# pressure.net
KiCad netlist of a schematic drawn in EAGLE
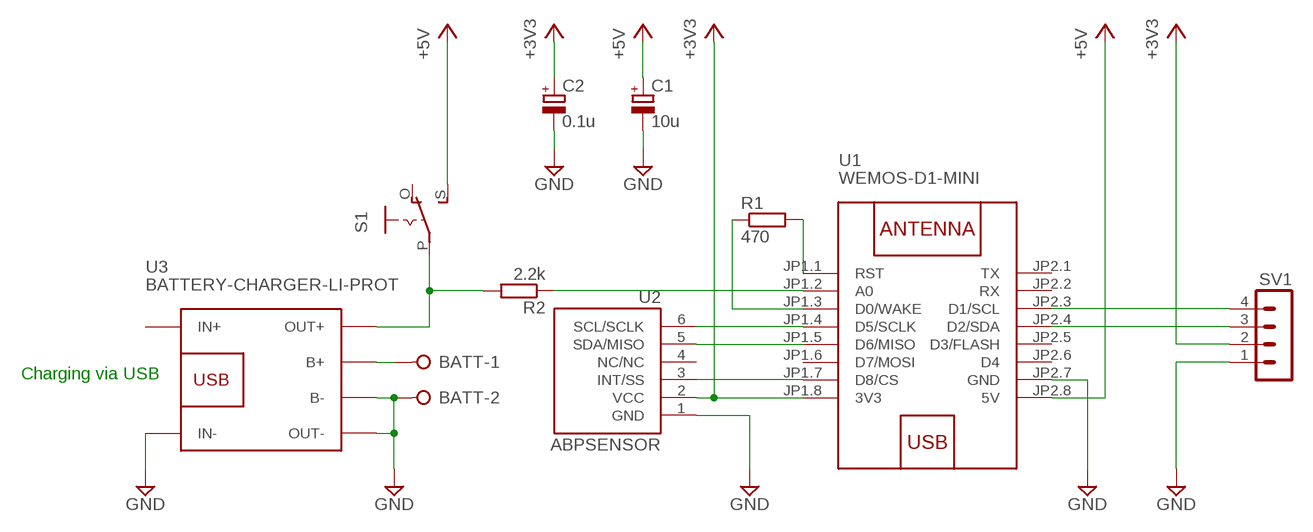
[diagram p0: schematic, sheet 1]

(export (version "E")
  (design (tool "Eeschema 10.0.6"))
  (components
    (comp (ref "BATT")
      (value "W237-02P")
      (footprint "eagle-import:W237-132")
      (libsource (lib "eagle-import") (part "W237-02P"))
    )
    (comp (ref "C1")
      (value "10u")
      (footprint "eagle-import:E2,5-5")
      (libsource (lib "eagle-import") (part "CPOL-EUE2.5-5"))
    )
    (comp (ref "C2")
      (value "0.1u")
      (footprint "eagle-import:E2,5-5")
      (libsource (lib "eagle-import") (part "CPOL-EUE2.5-5"))
    )
    (comp (ref "R1")
      (value "470")
      (footprint "eagle-import:0207_10")
      (libsource (lib "eagle-import") (part "R-EU_0207/10"))
    )
    (comp (ref "R2")
      (value "2.2k")
      (footprint "eagle-import:0207_10")
      (libsource (lib "eagle-import") (part "R-EU_0207/10"))
    )
    (comp (ref "S1")
      (value "EG1218S")
      (footprint "eagle-import:EG1218")
      (libsource (lib "eagle-import") (part "EG1218S"))
    )
    (comp (ref "SV1")
      (value "4-DIGIT-LED")
      (footprint "eagle-import:MA04-1")
      (libsource (lib "eagle-import") (part "MA04-1"))
    )
    (comp (ref "U1")
      (value "WEMOS-D1-MINI")
      (footprint "eagle-import:WEMOS-D1-MINI")
      (libsource (lib "eagle-import") (part "WEMOS-D1-MINI"))
    )
    (comp (ref "U2")
      (value "ABPSENSOR")
      (footprint "eagle-import:ABP-DIP6")
      (libsource (lib "eagle-import") (part "ABPSENSOR"))
    )
    (comp (ref "U3")
      (value "BATTERY-CHARGER-LI-PROT")
      (footprint "eagle-import:BATTERY-CHARGER-LI-PROT")
      (libsource (lib "eagle-import") (part "BATTERY-CHARGER-LI-PROT"))
    )
  )
  (nets
    (net (code "1") (name "+3V3") (class "Default")
      (node (ref "C2") (pin "+") (pinfunction "+_+") (pintype "passive"))
      (node (ref "SV1") (pin "2") (pinfunction "2_2") (pintype "passive"))
      (node (ref "U1") (pin "JP1.8") (pinfunction "3V3_JP1.8") (pintype "power_in"))
      (node (ref "U2") (pin "2") (pinfunction "VCC_2") (pintype "power_in"))
    )
    (net (code "2") (name "+5V") (class "Default")
      (node (ref "C1") (pin "+") (pinfunction "+_+") (pintype "passive"))
      (node (ref "S1") (pin "S") (pinfunction "S_S") (pintype "passive"))
      (node (ref "U1") (pin "JP2.8") (pinfunction "5V_JP2.8") (pintype "power_in"))
    )
    (net (code "3") (name "GND") (class "Default")
      (node (ref "BATT") (pin "2") (pinfunction "KL_2") (pintype "passive"))
      (node (ref "C1") (pin "-") (pinfunction "-_-") (pintype "passive"))
      (node (ref "C2") (pin "-") (pinfunction "-_-") (pintype "passive"))
      (node (ref "SV1") (pin "1") (pinfunction "1_1") (pintype "passive"))
      (node (ref "U1") (pin "JP2.7") (pinfunction "GND_JP2.7") (pintype "power_in"))
      (node (ref "U2") (pin "1") (pinfunction "GND_1") (pintype "power_in"))
      (node (ref "U3") (pin "B-") (pinfunction "B-_B-") (pintype "bidirectional"))
      (node (ref "U3") (pin "IN-") (pinfunction "IN-_IN-") (pintype "bidirectional"))
      (node (ref "U3") (pin "OUT-") (pinfunction "OUT-_OUT-") (pintype "bidirectional"))
    )
    (net (code "4") (name "Net-(BATTA-KL)") (class "Default")
      (node (ref "BATT") (pin "1") (pinfunction "KL_1") (pintype "passive"))
      (node (ref "U3") (pin "B+") (pinfunction "B+_B+") (pintype "bidirectional"))
    )
    (net (code "5") (name "Net-(R2-Pad2)") (class "Default")
      (node (ref "R2") (pin "2") (pinfunction "2_2") (pintype "passive"))
      (node (ref "S1") (pin "P") (pinfunction "P_P") (pintype "passive"))
      (node (ref "U3") (pin "OUT+") (pinfunction "OUT+_OUT+") (pintype "bidirectional"))
    )
    (net (code "6") (name "Net-(U1-A0)") (class "Default")
      (node (ref "R2") (pin "1") (pinfunction "1_1") (pintype "passive"))
      (node (ref "U1") (pin "JP1.2") (pinfunction "A0_JP1.2") (pintype "bidirectional"))
    )
    (net (code "7") (name "Net-(U1-D0{slash}WAKE)") (class "Default")
      (node (ref "R1") (pin "1") (pinfunction "1_1") (pintype "passive"))
      (node (ref "U1") (pin "JP1.3") (pinfunction "D0/WAKE_JP1.3") (pintype "bidirectional"))
    )
    (net (code "8") (name "Net-(U1-D1{slash}SCL)") (class "Default")
      (node (ref "SV1") (pin "4") (pinfunction "4_4") (pintype "passive"))
      (node (ref "U1") (pin "JP2.3") (pinfunction "D1/SCL_JP2.3") (pintype "bidirectional"))
    )
    (net (code "9") (name "Net-(U1-D2{slash}SDA)") (class "Default")
      (node (ref "SV1") (pin "3") (pinfunction "3_3") (pintype "passive"))
      (node (ref "U1") (pin "JP2.4") (pinfunction "D2/SDA_JP2.4") (pintype "bidirectional"))
    )
    (net (code "10") (name "Net-(U1-D5{slash}SCLK)") (class "Default")
      (node (ref "U1") (pin "JP1.4") (pinfunction "D5/SCLK_JP1.4") (pintype "bidirectional"))
      (node (ref "U2") (pin "6") (pinfunction "SCL/SCLK_6") (pintype "bidirectional"))
    )
    (net (code "11") (name "Net-(U1-D6{slash}MISO)") (class "Default")
      (node (ref "U1") (pin "JP1.5") (pinfunction "D6/MISO_JP1.5") (pintype "bidirectional"))
      (node (ref "U2") (pin "5") (pinfunction "SDA/MISO_5") (pintype "bidirectional"))
    )
    (net (code "12") (name "Net-(U1-D8{slash}CS)") (class "Default")
      (node (ref "U1") (pin "JP1.7") (pinfunction "D8/CS_JP1.7") (pintype "bidirectional"))
      (node (ref "U2") (pin "3") (pinfunction "INT/SS_3") (pintype "bidirectional"))
    )
    (net (code "13") (name "Net-(U1-RST)") (class "Default")
      (node (ref "R1") (pin "2") (pinfunction "2_2") (pintype "passive"))
      (node (ref "U1") (pin "JP1.1") (pinfunction "RST_JP1.1") (pintype "bidirectional"))
    )
    (net (code "14") (name "unconnected-(S1-PadO)") (class "Default")
      (node (ref "S1") (pin "O") (pinfunction "O_O") (pintype "passive"))
    )
    (net (code "15") (name "unconnected-(U1-D3{slash}FLASH-PadJP2.5)") (class "Default")
      (node (ref "U1") (pin "JP2.5") (pinfunction "D3/FLASH_JP2.5") (pintype "bidirectional"))
    )
    (net (code "16") (name "unconnected-(U1-D4-PadJP2.6)") (class "Default")
      (node (ref "U1") (pin "JP2.6") (pinfunction "D4_JP2.6") (pintype "bidirectional"))
    )
    (net (code "17") (name "unconnected-(U1-D7{slash}MOSI-PadJP1.6)") (class "Default")
      (node (ref "U1") (pin "JP1.6") (pinfunction "D7/MOSI_JP1.6") (pintype "bidirectional"))
    )
    (net (code "18") (name "unconnected-(U1-RX-PadJP2.2)") (class "Default")
      (node (ref "U1") (pin "JP2.2") (pinfunction "RX_JP2.2") (pintype "bidirectional"))
    )
    (net (code "19") (name "unconnected-(U1-TX-PadJP2.1)") (class "Default")
      (node (ref "U1") (pin "JP2.1") (pinfunction "TX_JP2.1") (pintype "bidirectional"))
    )
    (net (code "20") (name "unconnected-(U2-NC{slash}NC-Pad4)") (class "Default")
      (node (ref "U2") (pin "4") (pinfunction "NC/NC_4") (pintype "bidirectional"))
    )
    (net (code "21") (name "unconnected-(U3-PadIN+)") (class "Default")
      (node (ref "U3") (pin "IN+") (pinfunction "IN+_IN+") (pintype "bidirectional"))
    )
  )
)
